# Sheet_1_2025-09-27.net
KiCad netlist of a schematic drawn in Altium Designer
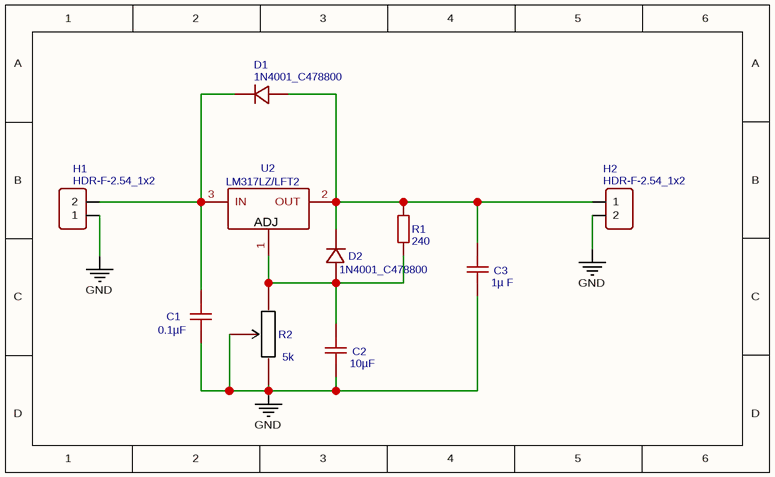
[diagram p0: Sheet_1_2025-09-27.schdoc]

(export (version "E")
  (design (tool "Eeschema 10.0.6"))
  (components
    (comp (ref "C1")
      (value "0.1µF")
      (fields (field (name "MANUFACTURER") "ReliaPro") (field (name "MANUFACTURER PART") "472M 1KV"))
      (libsource (lib "altium-import") (part "root_1_0.1µF_"))
    )
    (comp (ref "C2")
      (value "10µF")
      (fields (field (name "MANUFACTURER") "ReliaPro") (field (name "MANUFACTURER PART") "472M 1KV"))
      (libsource (lib "altium-import") (part "root_1_10µF_"))
    )
    (comp (ref "C3")
      (value "1µ F")
      (fields (field (name "MANUFACTURER") "ReliaPro") (field (name "MANUFACTURER PART") "472M 1KV"))
      (libsource (lib "altium-import") (part "root_1_1µ F_"))
    )
    (comp (ref "D1")
      (value "1N4001_C478800")
      (fields
        (field (name "MANUFACTURER") "JF")
        (field (name "MANUFACTURER PART") "1N4001")
        (field (name "CONTRIBUTOR") "LCSC")
      )
      (libsource (lib "altium-import") (part "root_0_1N4001_C478800_"))
    )
    (comp (ref "D2")
      (value "1N4001_C478800")
      (fields
        (field (name "MANUFACTURER") "JF")
        (field (name "MANUFACTURER PART") "1N4001")
        (field (name "CONTRIBUTOR") "LCSC")
      )
      (libsource (lib "altium-import") (part "root_3_1N4001_C478800_"))
    )
    (comp (ref "H1")
      (value "HDR-F-2.54_1x2")
      (fields (field (name "CONTRIBUTOR") "LCEDA_Lib"))
      (libsource (lib "altium-import") (part "root_2_HDR-F-2.54_1x2_"))
    )
    (comp (ref "H2")
      (value "HDR-F-2.54_1x2")
      (fields (field (name "CONTRIBUTOR") "LCEDA_Lib"))
      (libsource (lib "altium-import") (part "root_0_HDR-F-2.54_1x2_"))
    )
    (comp (ref "R1")
      (value "240")
      (fields (field (name "MANUFACTURER") "Chian Chia Elec") (field (name "CONTRIBUTOR") "LCSC"))
      (libsource (lib "altium-import") (part "root_1_240_"))
    )
    (comp (ref "R2")
      (value "5k")
      (fields
        (field (name "MANUFACTURER PART") "Small potenciometer")
        (field (name "CONTRIBUTOR") "LewisMojica")
      )
      (libsource (lib "altium-import") (part "root_0_5k_"))
    )
    (comp (ref "U2")
      (value "LM317LZ/LFT2")
      (fields (field (name "MANUFACTURER") "TI(德州仪器)") (field (name "CONTRIBUTOR") "lcsc"))
      (libsource (lib "altium-import") (part "root_0_LM317LZ/LFT2_"))
    )
  )
  (nets
    (net (code "1") (name "GND") (class "Default")
      (node (ref "C1") (pin "1") (pinfunction "1_1") (pintype "passive"))
      (node (ref "C2") (pin "1") (pinfunction "1_1") (pintype "passive"))
      (node (ref "C3") (pin "1") (pinfunction "1_1") (pintype "passive"))
      (node (ref "H1") (pin "1") (pinfunction "1_1") (pintype "passive"))
      (node (ref "H2") (pin "2") (pinfunction "2_2") (pintype "passive"))
      (node (ref "R2") (pin "2") (pinfunction "2_2") (pintype "passive"))
      (node (ref "R2") (pin "3") (pinfunction "3_3") (pintype "passive"))
    )
    (net (code "2") (name "Net-(D1-1)") (class "Default")
      (node (ref "C1") (pin "2") (pinfunction "2_2") (pintype "passive"))
      (node (ref "D1") (pin "C") (pinfunction "1_C") (pintype "passive"))
      (node (ref "H1") (pin "2") (pinfunction "2_2") (pintype "passive"))
      (node (ref "U2") (pin "3") (pinfunction "IN_3") (pintype "passive"))
    )
    (net (code "3") (name "Net-(D1-2)") (class "Default")
      (node (ref "C3") (pin "2") (pinfunction "2_2") (pintype "passive"))
      (node (ref "D1") (pin "A") (pinfunction "2_A") (pintype "passive"))
      (node (ref "D2") (pin "C") (pinfunction "1_C") (pintype "passive"))
      (node (ref "H2") (pin "1") (pinfunction "1_1") (pintype "passive"))
      (node (ref "R1") (pin "2") (pinfunction "2_2") (pintype "passive"))
      (node (ref "U2") (pin "2") (pinfunction "OUT_2") (pintype "passive"))
    )
    (net (code "4") (name "Net-(D2-2)") (class "Default")
      (node (ref "C2") (pin "2") (pinfunction "2_2") (pintype "passive"))
      (node (ref "D2") (pin "A") (pinfunction "2_A") (pintype "passive"))
      (node (ref "R1") (pin "1") (pinfunction "1_1") (pintype "passive"))
      (node (ref "R2") (pin "1") (pinfunction "1_1") (pintype "passive"))
      (node (ref "U2") (pin "1") (pinfunction "ADJ_1") (pintype "passive"))
    )
  )
)
